# RS485_Port.net
KiCad netlist of a schematic drawn in Altium Designer
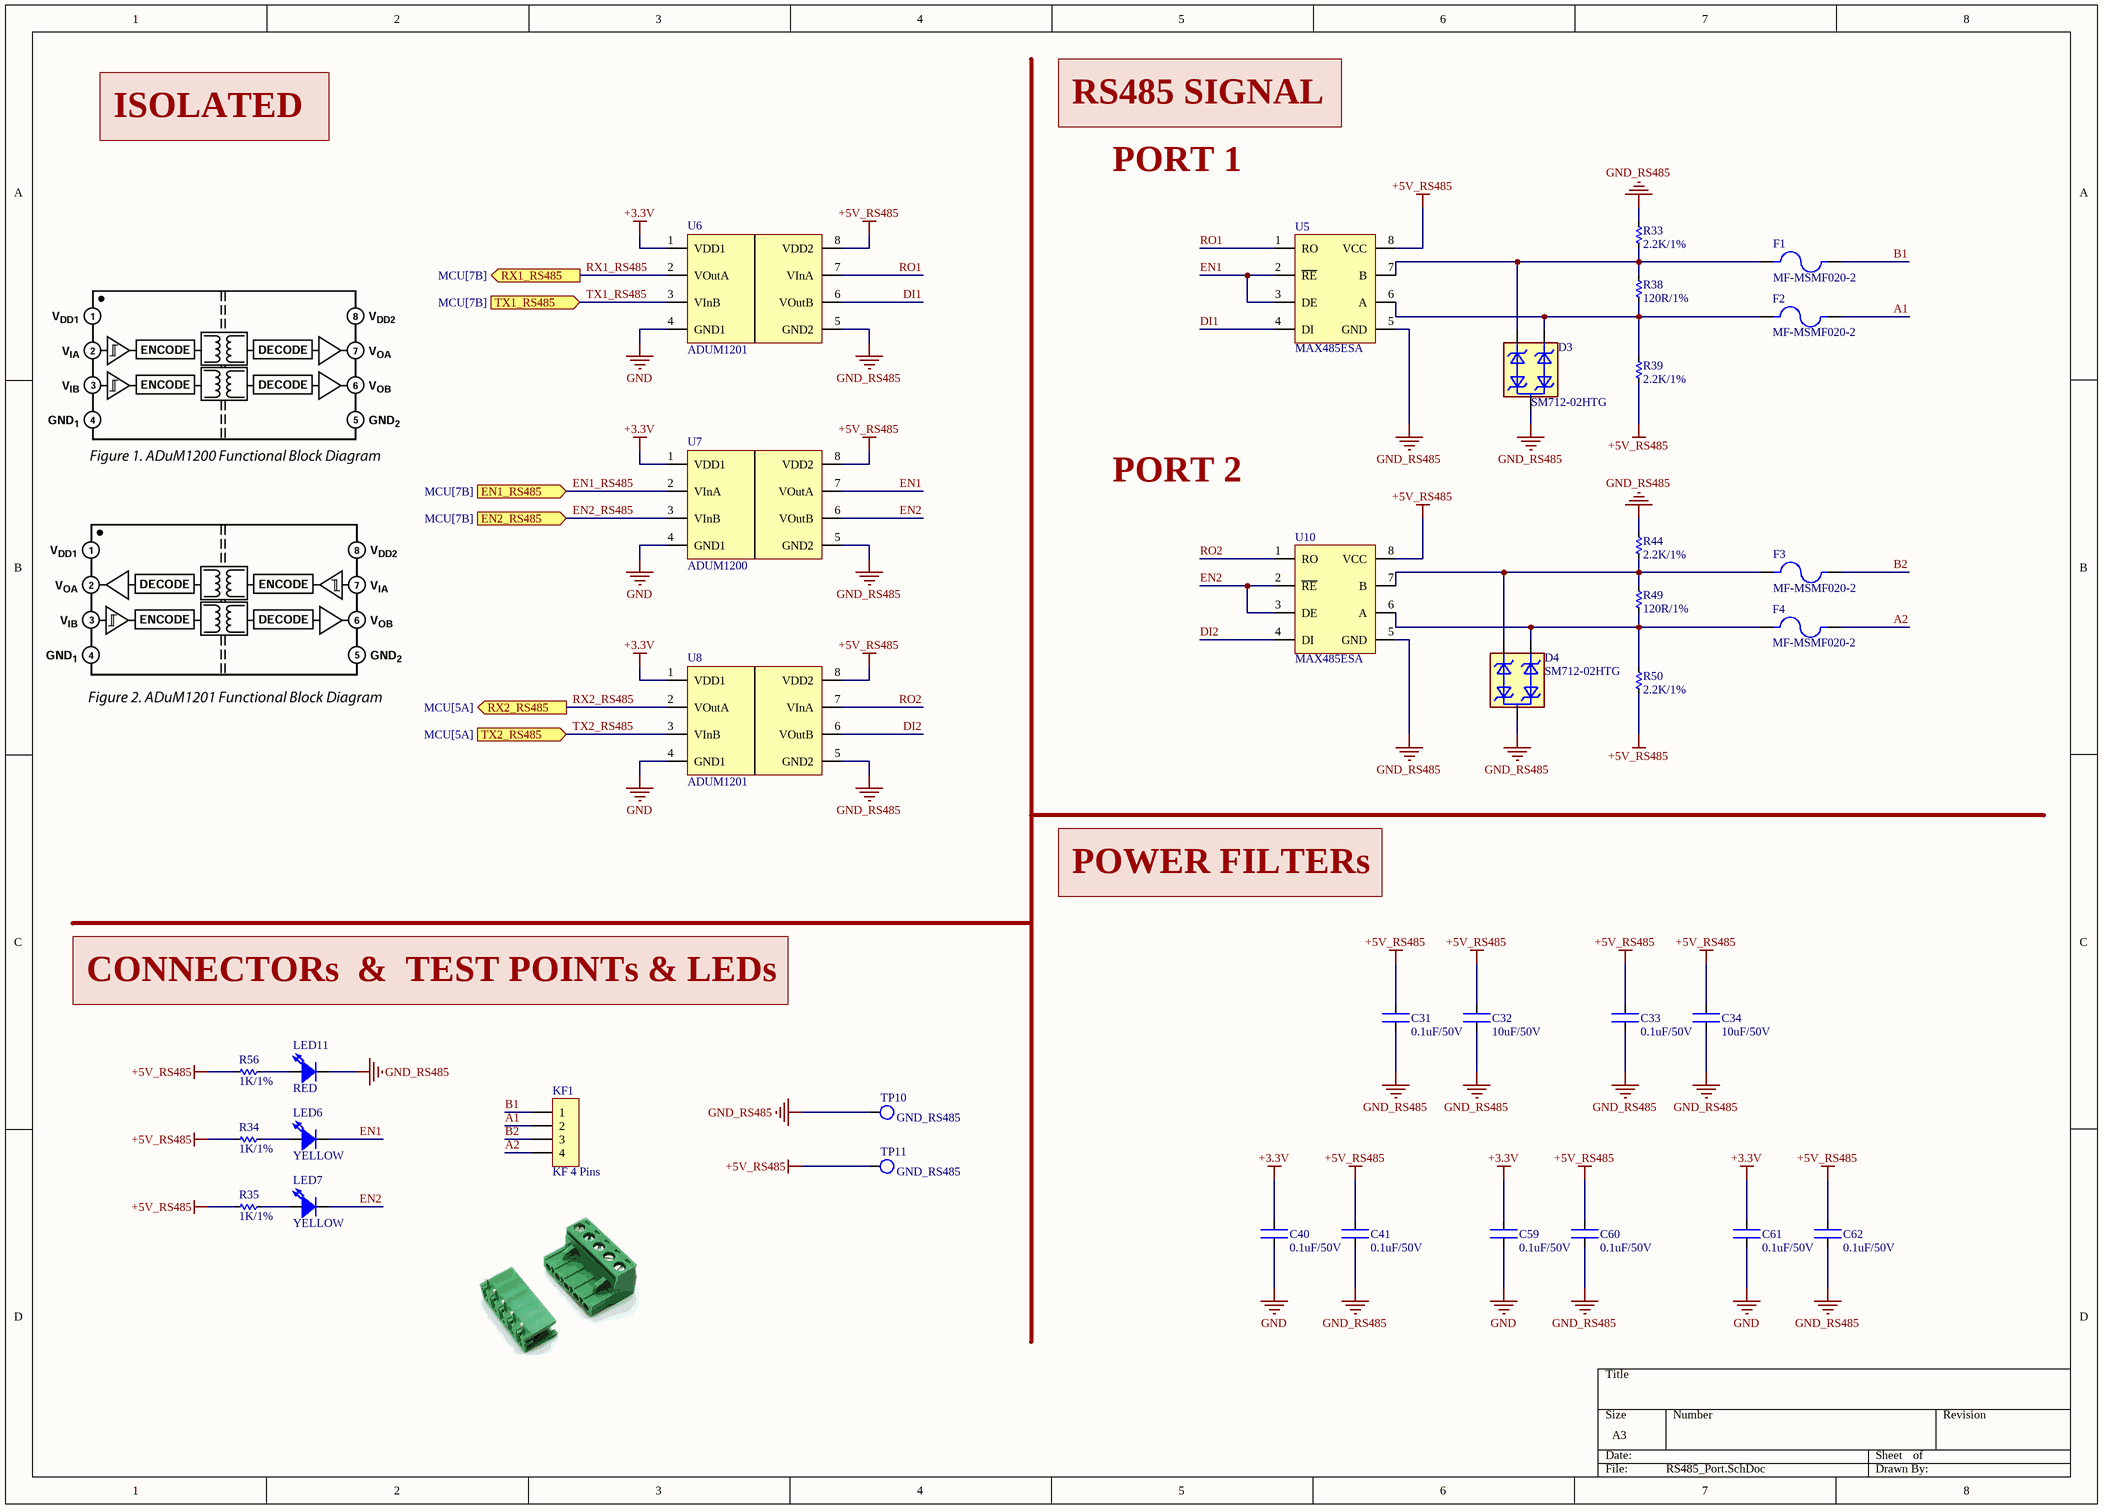
[diagram p0: RS485_Port.SchDoc]

(export (version "E")
  (design (tool "Eeschema 10.0.6"))
  (components
    (comp (ref "C31")
      (value "0.1uF/50V")
      (footprint "CAP - 0603")
      (description "CAPACITOR SMD - KEMET")
      (libsource (lib "NewLibrary") (part "CAPACITOR"))
    )
    (comp (ref "C32")
      (value "10uF/50V")
      (footprint "CAP - 0603")
      (description "CAPACITOR SMD - KEMET")
      (libsource (lib "NewLibrary") (part "CAPACITOR"))
    )
    (comp (ref "C33")
      (value "0.1uF/50V")
      (footprint "CAP - 0603")
      (description "CAPACITOR SMD - KEMET")
      (libsource (lib "NewLibrary") (part "CAPACITOR"))
    )
    (comp (ref "C34")
      (value "10uF/50V")
      (footprint "CAP - 0603")
      (description "CAPACITOR SMD - KEMET")
      (libsource (lib "NewLibrary") (part "CAPACITOR"))
    )
    (comp (ref "C40")
      (value "0.1uF/50V")
      (footprint "CAP - 0603")
      (description "CAPACITOR SMD - KEMET")
      (libsource (lib "NewLibrary") (part "CAPACITOR"))
    )
    (comp (ref "C41")
      (value "0.1uF/50V")
      (footprint "CAP - 0603")
      (description "CAPACITOR SMD - KEMET")
      (libsource (lib "NewLibrary") (part "CAPACITOR"))
    )
    (comp (ref "C59")
      (value "0.1uF/50V")
      (footprint "CAP - 0603")
      (description "CAPACITOR SMD - KEMET")
      (libsource (lib "NewLibrary") (part "CAPACITOR"))
    )
    (comp (ref "C60")
      (value "0.1uF/50V")
      (footprint "CAP - 0603")
      (description "CAPACITOR SMD - KEMET")
      (libsource (lib "NewLibrary") (part "CAPACITOR"))
    )
    (comp (ref "C61")
      (value "0.1uF/50V")
      (footprint "CAP - 0603")
      (description "CAPACITOR SMD - KEMET")
      (libsource (lib "NewLibrary") (part "CAPACITOR"))
    )
    (comp (ref "C62")
      (value "0.1uF/50V")
      (footprint "CAP - 0603")
      (description "CAPACITOR SMD - KEMET")
      (libsource (lib "NewLibrary") (part "CAPACITOR"))
    )
    (comp (ref "D3")
      (value "SM712-02HTG")
      (footprint "SOT23-3")
      (libsource (lib "NewLibrary") (part "SM712-02HTG"))
    )
    (comp (ref "D4")
      (value "SM712-02HTG")
      (footprint "SOT23-3")
      (libsource (lib "NewLibrary") (part "SM712-02HTG"))
    )
    (comp (ref "F1")
      (value "MF-MSMF020-2")
      (footprint "Fuse 4.55x3.24 mm")
      (description "Fuse Resettable 30V/0.2A; Size 4.55 x 3.24mm")
      (libsource (lib "NewLibrary") (part "MF-MSMF020-2"))
    )
    (comp (ref "F2")
      (value "MF-MSMF020-2")
      (footprint "Fuse 4.55x3.24 mm")
      (description "Fuse Resettable 30V/0.2A; Size 4.55 x 3.24mm")
      (libsource (lib "NewLibrary") (part "MF-MSMF020-2"))
    )
    (comp (ref "F3")
      (value "MF-MSMF020-2")
      (footprint "Fuse 4.55x3.24 mm")
      (description "Fuse Resettable 30V/0.2A; Size 4.55 x 3.24mm")
      (libsource (lib "NewLibrary") (part "MF-MSMF020-2"))
    )
    (comp (ref "F4")
      (value "MF-MSMF020-2")
      (footprint "Fuse 4.55x3.24 mm")
      (description "Fuse Resettable 30V/0.2A; Size 4.55 x 3.24mm")
      (libsource (lib "NewLibrary") (part "MF-MSMF020-2"))
    )
    (comp (ref "KF1")
      (value "KF 4 Pins")
      (footprint "KF_4")
      (description "KF Terminal Block Plug-in")
      (libsource (lib "NewLibrary") (part "KF 4 Pins"))
    )
    (comp (ref "LED6")
      (value "YELLOW")
      (footprint "YELLOW_LED_0805")
      (description "LED SMD")
      (libsource (lib "NewLibrary") (part "LED_SMD"))
    )
    (comp (ref "LED7")
      (value "YELLOW")
      (footprint "YELLOW_LED_0805")
      (description "LED SMD")
      (libsource (lib "NewLibrary") (part "LED_SMD"))
    )
    (comp (ref "LED11")
      (value "RED")
      (footprint "RED_LED_0603")
      (description "LED SMD")
      (libsource (lib "NewLibrary") (part "LED_SMD"))
    )
    (comp (ref "R33")
      (value "2.2K/1%")
      (footprint "RES - 0603")
      (description "Resistor SMD - YAGEO")
      (libsource (lib "NewLibrary") (part "RESISTOR"))
    )
    (comp (ref "R34")
      (value "1K/1%")
      (footprint "RES - 0603")
      (description "Resistor SMD - YAGEO")
      (libsource (lib "NewLibrary") (part "RESISTOR"))
    )
    (comp (ref "R35")
      (value "1K/1%")
      (footprint "RES - 0603")
      (description "Resistor SMD - YAGEO")
      (libsource (lib "NewLibrary") (part "RESISTOR"))
    )
    (comp (ref "R38")
      (value "120R/1%")
      (footprint "RES - 0603")
      (description "Resistor SMD - YAGEO")
      (libsource (lib "NewLibrary") (part "RESISTOR"))
    )
    (comp (ref "R39")
      (value "2.2K/1%")
      (footprint "RES - 0603")
      (description "Resistor SMD - YAGEO")
      (libsource (lib "NewLibrary") (part "RESISTOR"))
    )
    (comp (ref "R44")
      (value "2.2K/1%")
      (footprint "RES - 0603")
      (description "Resistor SMD - YAGEO")
      (libsource (lib "NewLibrary") (part "RESISTOR"))
    )
    (comp (ref "R49")
      (value "120R/1%")
      (footprint "RES - 0603")
      (description "Resistor SMD - YAGEO")
      (libsource (lib "NewLibrary") (part "RESISTOR"))
    )
    (comp (ref "R50")
      (value "2.2K/1%")
      (footprint "RES - 0603")
      (description "Resistor SMD - YAGEO")
      (libsource (lib "NewLibrary") (part "RESISTOR"))
    )
    (comp (ref "R56")
      (value "1K/1%")
      (footprint "RES - 0603")
      (description "Resistor SMD - YAGEO")
      (libsource (lib "NewLibrary") (part "RESISTOR"))
    )
    (comp (ref "TP10")
      (value "GND_RS485")
      (footprint "Test Point")
      (description "Test Point")
      (libsource (lib "NewLibrary") (part "TEST POINT"))
    )
    (comp (ref "TP11")
      (value "GND_RS485")
      (footprint "Test Point")
      (description "Test Point")
      (libsource (lib "NewLibrary") (part "TEST POINT"))
    )
    (comp (ref "U5")
      (value "MAX485ESA")
      (footprint "SOP_8")
      (description "1/1 Transceiver Half RS422, RS485")
      (libsource (lib "NewLibrary") (part "MAX485ESA"))
    )
    (comp (ref "U6")
      (value "ADUM1201")
      (footprint "SOP_8")
      (description "Dual-Channel Digital Isolators, General Purpose Digital Isolator 2500Vrms 2 Channel 1Mbps 25kV/µs")
      (libsource (lib "NewLibrary") (part "ADUM1201"))
    )
    (comp (ref "U7")
      (value "ADUM1200")
      (footprint "SOP_8")
      (description "Dual-Channel Digital Isolators, General Purpose Digital Isolator 2500Vrms 2 Channel 1Mbps 25kV/µs")
      (libsource (lib "NewLibrary") (part "ADUM1200"))
    )
    (comp (ref "U8")
      (value "ADUM1201")
      (footprint "SOP_8")
      (description "Dual-Channel Digital Isolators, General Purpose Digital Isolator 2500Vrms 2 Channel 1Mbps 25kV/µs")
      (libsource (lib "NewLibrary") (part "ADUM1201"))
    )
    (comp (ref "U10")
      (value "MAX485ESA")
      (footprint "SOP_8")
      (description "1/1 Transceiver Half RS422, RS485")
      (libsource (lib "NewLibrary") (part "MAX485ESA"))
    )
  )
  (nets
    (net (code "1") (name "+3.3V") (class "Default")
      (node (ref "C40") (pin "1") (pinfunction "1_1") (pintype "passive"))
      (node (ref "C59") (pin "1") (pinfunction "1_1") (pintype "passive"))
      (node (ref "C61") (pin "1") (pinfunction "1_1") (pintype "passive"))
      (node (ref "U6") (pin "1") (pinfunction "VDD1_1") (pintype "passive"))
      (node (ref "U7") (pin "1") (pinfunction "VDD1_1") (pintype "passive"))
      (node (ref "U8") (pin "1") (pinfunction "VDD1_1") (pintype "passive"))
    )
    (net (code "2") (name "+5V_RS485") (class "Default")
      (node (ref "C31") (pin "1") (pinfunction "1_1") (pintype "passive"))
      (node (ref "C32") (pin "1") (pinfunction "1_1") (pintype "passive"))
      (node (ref "C33") (pin "1") (pinfunction "1_1") (pintype "passive"))
      (node (ref "C34") (pin "1") (pinfunction "1_1") (pintype "passive"))
      (node (ref "C41") (pin "1") (pinfunction "1_1") (pintype "passive"))
      (node (ref "C60") (pin "1") (pinfunction "1_1") (pintype "passive"))
      (node (ref "C62") (pin "1") (pinfunction "1_1") (pintype "passive"))
      (node (ref "R34") (pin "1") (pinfunction "1_1") (pintype "passive"))
      (node (ref "R35") (pin "1") (pinfunction "1_1") (pintype "passive"))
      (node (ref "R39") (pin "1") (pinfunction "1_1") (pintype "passive"))
      (node (ref "R50") (pin "1") (pinfunction "1_1") (pintype "passive"))
      (node (ref "R56") (pin "1") (pinfunction "1_1") (pintype "passive"))
      (node (ref "TP11") (pin "1") (pinfunction "1_1") (pintype "passive"))
      (node (ref "U10") (pin "8") (pinfunction "VCC_8") (pintype "passive"))
      (node (ref "U5") (pin "8") (pinfunction "VCC_8") (pintype "passive"))
      (node (ref "U6") (pin "8") (pinfunction "VDD2_8") (pintype "passive"))
      (node (ref "U7") (pin "8") (pinfunction "VDD2_8") (pintype "passive"))
      (node (ref "U8") (pin "8") (pinfunction "VDD2_8") (pintype "passive"))
    )
    (net (code "3") (name "/A1") (class "Default")
      (node (ref "F2") (pin "2") (pinfunction "2_2") (pintype "passive"))
      (node (ref "KF1") (pin "2") (pinfunction "2_2") (pintype "passive"))
    )
    (net (code "4") (name "/A2") (class "Default")
      (node (ref "F4") (pin "2") (pinfunction "2_2") (pintype "passive"))
      (node (ref "KF1") (pin "4") (pinfunction "4_4") (pintype "passive"))
    )
    (net (code "5") (name "/B1") (class "Default")
      (node (ref "F1") (pin "2") (pinfunction "2_2") (pintype "passive"))
      (node (ref "KF1") (pin "1") (pinfunction "1_1") (pintype "passive"))
    )
    (net (code "6") (name "/B2") (class "Default")
      (node (ref "F3") (pin "2") (pinfunction "2_2") (pintype "passive"))
      (node (ref "KF1") (pin "3") (pinfunction "3_3") (pintype "passive"))
    )
    (net (code "7") (name "/DI1") (class "Default")
      (node (ref "U5") (pin "4") (pinfunction "DI_4") (pintype "passive"))
      (node (ref "U6") (pin "6") (pinfunction "VOutB_6") (pintype "passive"))
    )
    (net (code "8") (name "/DI2") (class "Default")
      (node (ref "U10") (pin "4") (pinfunction "DI_4") (pintype "passive"))
      (node (ref "U8") (pin "6") (pinfunction "VOutB_6") (pintype "passive"))
    )
    (net (code "9") (name "/EN1") (class "Default")
      (node (ref "LED6") (pin "2") (pinfunction "2_2") (pintype "passive"))
      (node (ref "U5") (pin "2") (pinfunction "~{RE}_2") (pintype "passive"))
      (node (ref "U5") (pin "3") (pinfunction "DE_3") (pintype "passive"))
      (node (ref "U7") (pin "7") (pinfunction "VOutA_7") (pintype "passive"))
    )
    (net (code "10") (name "/EN1_RS485") (class "Default")
      (node (ref "U7") (pin "2") (pinfunction "VInA_2") (pintype "passive"))
    )
    (net (code "11") (name "/EN2") (class "Default")
      (node (ref "LED7") (pin "2") (pinfunction "2_2") (pintype "passive"))
      (node (ref "U10") (pin "2") (pinfunction "~{RE}_2") (pintype "passive"))
      (node (ref "U10") (pin "3") (pinfunction "DE_3") (pintype "passive"))
      (node (ref "U7") (pin "6") (pinfunction "VOutB_6") (pintype "passive"))
    )
    (net (code "12") (name "/EN2_RS485") (class "Default")
      (node (ref "U7") (pin "3") (pinfunction "VInB_3") (pintype "passive"))
    )
    (net (code "13") (name "/RO1") (class "Default")
      (node (ref "U5") (pin "1") (pinfunction "RO_1") (pintype "passive"))
      (node (ref "U6") (pin "7") (pinfunction "VInA_7") (pintype "passive"))
    )
    (net (code "14") (name "/RO2") (class "Default")
      (node (ref "U10") (pin "1") (pinfunction "RO_1") (pintype "passive"))
      (node (ref "U8") (pin "7") (pinfunction "VInA_7") (pintype "passive"))
    )
    (net (code "15") (name "/RX1_RS485") (class "Default")
      (node (ref "U6") (pin "2") (pinfunction "VOutA_2") (pintype "passive"))
    )
    (net (code "16") (name "/RX2_RS485") (class "Default")
      (node (ref "U8") (pin "2") (pinfunction "VOutA_2") (pintype "passive"))
    )
    (net (code "17") (name "/TX1_RS485") (class "Default")
      (node (ref "U6") (pin "3") (pinfunction "VInB_3") (pintype "passive"))
    )
    (net (code "18") (name "/TX2_RS485") (class "Default")
      (node (ref "U8") (pin "3") (pinfunction "VInB_3") (pintype "passive"))
    )
    (net (code "19") (name "GND") (class "Default")
      (node (ref "C40") (pin "2") (pinfunction "2_2") (pintype "passive"))
      (node (ref "C59") (pin "2") (pinfunction "2_2") (pintype "passive"))
      (node (ref "C61") (pin "2") (pinfunction "2_2") (pintype "passive"))
      (node (ref "U6") (pin "4") (pinfunction "GND1_4") (pintype "passive"))
      (node (ref "U7") (pin "4") (pinfunction "GND1_4") (pintype "passive"))
      (node (ref "U8") (pin "4") (pinfunction "GND1_4") (pintype "passive"))
    )
    (net (code "20") (name "GND_RS485") (class "Default")
      (node (ref "C31") (pin "2") (pinfunction "2_2") (pintype "passive"))
      (node (ref "C32") (pin "2") (pinfunction "2_2") (pintype "passive"))
      (node (ref "C33") (pin "2") (pinfunction "2_2") (pintype "passive"))
      (node (ref "C34") (pin "2") (pinfunction "2_2") (pintype "passive"))
      (node (ref "C41") (pin "2") (pinfunction "2_2") (pintype "passive"))
      (node (ref "C60") (pin "2") (pinfunction "2_2") (pintype "passive"))
      (node (ref "C62") (pin "2") (pinfunction "2_2") (pintype "passive"))
      (node (ref "D3") (pin "3") (pinfunction "3_3") (pintype "passive"))
      (node (ref "D4") (pin "3") (pinfunction "3_3") (pintype "passive"))
      (node (ref "LED11") (pin "2") (pinfunction "2_2") (pintype "passive"))
      (node (ref "R33") (pin "2") (pinfunction "2_2") (pintype "passive"))
      (node (ref "R44") (pin "2") (pinfunction "2_2") (pintype "passive"))
      (node (ref "TP10") (pin "1") (pinfunction "1_1") (pintype "passive"))
      (node (ref "U10") (pin "5") (pinfunction "GND_5") (pintype "passive"))
      (node (ref "U5") (pin "5") (pinfunction "GND_5") (pintype "passive"))
      (node (ref "U6") (pin "5") (pinfunction "GND2_5") (pintype "passive"))
      (node (ref "U7") (pin "5") (pinfunction "GND2_5") (pintype "passive"))
      (node (ref "U8") (pin "5") (pinfunction "GND2_5") (pintype "passive"))
    )
    (net (code "21") (name "Net-(LED6-Pad1)") (class "Default")
      (node (ref "LED6") (pin "1") (pinfunction "1_1") (pintype "passive"))
      (node (ref "R34") (pin "2") (pinfunction "2_2") (pintype "passive"))
    )
    (net (code "22") (name "Net-(LED7-Pad1)") (class "Default")
      (node (ref "LED7") (pin "1") (pinfunction "1_1") (pintype "passive"))
      (node (ref "R35") (pin "2") (pinfunction "2_2") (pintype "passive"))
    )
    (net (code "23") (name "Net-(LED11-Pad1)") (class "Default")
      (node (ref "LED11") (pin "1") (pinfunction "1_1") (pintype "passive"))
      (node (ref "R56") (pin "2") (pinfunction "2_2") (pintype "passive"))
    )
    (net (code "24") (name "Net-(U5-A)") (class "Default")
      (node (ref "D3") (pin "1") (pinfunction "1_1") (pintype "passive"))
      (node (ref "F2") (pin "1") (pinfunction "1_1") (pintype "passive"))
      (node (ref "R38") (pin "1") (pinfunction "1_1") (pintype "passive"))
      (node (ref "R39") (pin "2") (pinfunction "2_2") (pintype "passive"))
      (node (ref "U5") (pin "6") (pinfunction "A_6") (pintype "passive"))
    )
    (net (code "25") (name "Net-(U5-B)") (class "Default")
      (node (ref "D3") (pin "2") (pinfunction "2_2") (pintype "passive"))
      (node (ref "F1") (pin "1") (pinfunction "1_1") (pintype "passive"))
      (node (ref "R33") (pin "1") (pinfunction "1_1") (pintype "passive"))
      (node (ref "R38") (pin "2") (pinfunction "2_2") (pintype "passive"))
      (node (ref "U5") (pin "7") (pinfunction "B_7") (pintype "passive"))
    )
    (net (code "26") (name "Net-(U10-A)") (class "Default")
      (node (ref "D4") (pin "1") (pinfunction "1_1") (pintype "passive"))
      (node (ref "F4") (pin "1") (pinfunction "1_1") (pintype "passive"))
      (node (ref "R49") (pin "1") (pinfunction "1_1") (pintype "passive"))
      (node (ref "R50") (pin "2") (pinfunction "2_2") (pintype "passive"))
      (node (ref "U10") (pin "6") (pinfunction "A_6") (pintype "passive"))
    )
    (net (code "27") (name "Net-(U10-B)") (class "Default")
      (node (ref "D4") (pin "2") (pinfunction "2_2") (pintype "passive"))
      (node (ref "F3") (pin "1") (pinfunction "1_1") (pintype "passive"))
      (node (ref "R44") (pin "1") (pinfunction "1_1") (pintype "passive"))
      (node (ref "R49") (pin "2") (pinfunction "2_2") (pintype "passive"))
      (node (ref "U10") (pin "7") (pinfunction "B_7") (pintype "passive"))
    )
  )
)
